# 222.net
KiCad netlist of a schematic drawn in Altium Designer
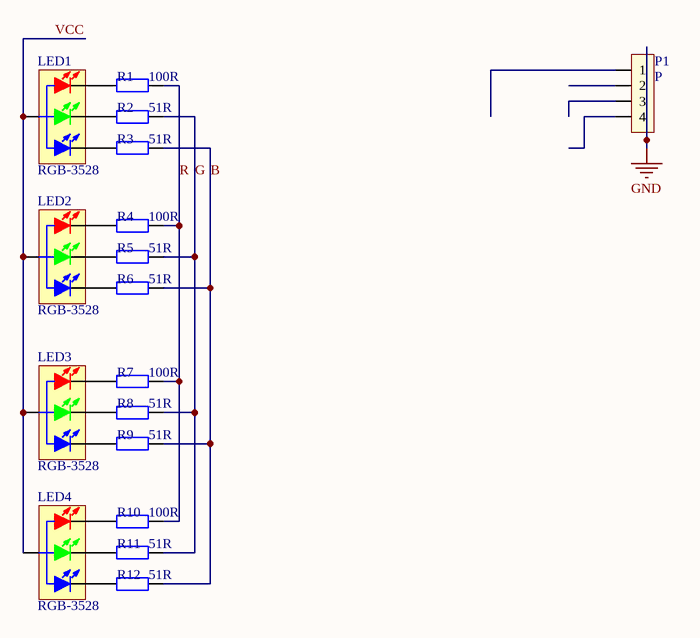
[diagram p0: 222.SchDoc]

(export (version "E")
  (design (tool "Eeschema 10.0.6"))
  (components
    (comp (ref "LED1")
      (value "RGB-3528")
      (footprint "LED 3528-4Pin")
      (description "三基色LED")
      (libsource (lib "9.1   - LED") (part "LED-RGB-3528"))
    )
    (comp (ref "LED2")
      (value "RGB-3528")
      (footprint "LED 3528-4Pin")
      (description "三基色LED")
      (libsource (lib "9.1   - LED") (part "LED-RGB-3528"))
    )
    (comp (ref "LED3")
      (value "RGB-3528")
      (footprint "LED 3528-4Pin")
      (description "三基色LED")
      (libsource (lib "9.1   - LED") (part "LED-RGB-3528"))
    )
    (comp (ref "LED4")
      (value "RGB-3528")
      (footprint "LED 3528-4Pin")
      (description "三基色LED")
      (libsource (lib "9.1   - LED") (part "LED-RGB-3528"))
    )
    (comp (ref "P1") (value "P") (footprint "SH1.0_4pin") (libsource (lib "0") (part "SH1.0-4")))
    (comp (ref "R1")
      (value "100R")
      (footprint "0603-1")
      (description "贴片电阻")
      (fields (field (name "Comment") "Res1") (field (name "PUBLISHER") "Altium Limited"))
      (libsource (lib "fszhang") (part "Res1"))
    )
    (comp (ref "R2")
      (value "51R")
      (footprint "0603-1")
      (description "贴片电阻")
      (fields (field (name "Comment") "Res1") (field (name "PUBLISHER") "Altium Limited"))
      (libsource (lib "fszhang") (part "Res1"))
    )
    (comp (ref "R3")
      (value "51R")
      (footprint "0603-1")
      (description "贴片电阻")
      (fields (field (name "Comment") "Res1") (field (name "PUBLISHER") "Altium Limited"))
      (libsource (lib "fszhang") (part "Res1"))
    )
    (comp (ref "R4")
      (value "100R")
      (footprint "0603-1")
      (description "贴片电阻")
      (fields (field (name "Comment") "Res1") (field (name "PUBLISHER") "Altium Limited"))
      (libsource (lib "fszhang") (part "Res1"))
    )
    (comp (ref "R5")
      (value "51R")
      (footprint "0603-1")
      (description "贴片电阻")
      (fields (field (name "Comment") "Res1") (field (name "PUBLISHER") "Altium Limited"))
      (libsource (lib "fszhang") (part "Res1"))
    )
    (comp (ref "R6")
      (value "51R")
      (footprint "0603-1")
      (description "贴片电阻")
      (fields (field (name "Comment") "Res1") (field (name "PUBLISHER") "Altium Limited"))
      (libsource (lib "fszhang") (part "Res1"))
    )
    (comp (ref "R7")
      (value "100R")
      (footprint "0603-1")
      (description "贴片电阻")
      (fields (field (name "Comment") "Res1") (field (name "PUBLISHER") "Altium Limited"))
      (libsource (lib "fszhang") (part "Res1"))
    )
    (comp (ref "R8")
      (value "51R")
      (footprint "0603-1")
      (description "贴片电阻")
      (fields (field (name "Comment") "Res1") (field (name "PUBLISHER") "Altium Limited"))
      (libsource (lib "fszhang") (part "Res1"))
    )
    (comp (ref "R9")
      (value "51R")
      (footprint "0603-1")
      (description "贴片电阻")
      (fields (field (name "Comment") "Res1") (field (name "PUBLISHER") "Altium Limited"))
      (libsource (lib "fszhang") (part "Res1"))
    )
    (comp (ref "R10")
      (value "100R")
      (footprint "0603-1")
      (description "贴片电阻")
      (fields (field (name "Comment") "Res1") (field (name "PUBLISHER") "Altium Limited"))
      (libsource (lib "fszhang") (part "Res1"))
    )
    (comp (ref "R11")
      (value "51R")
      (footprint "0603-1")
      (description "贴片电阻")
      (fields (field (name "Comment") "Res1") (field (name "PUBLISHER") "Altium Limited"))
      (libsource (lib "fszhang") (part "Res1"))
    )
    (comp (ref "R12")
      (value "51R")
      (footprint "0603-1")
      (description "贴片电阻")
      (fields (field (name "Comment") "Res1") (field (name "PUBLISHER") "Altium Limited"))
      (libsource (lib "fszhang") (part "Res1"))
    )
  )
  (nets
    (net (code "1") (name "/B") (class "Default")
      (node (ref "R12") (pin "2") (pinfunction "2_2") (pintype "passive"))
      (node (ref "R3") (pin "2") (pinfunction "2_2") (pintype "passive"))
      (node (ref "R6") (pin "2") (pinfunction "2_2") (pintype "passive"))
      (node (ref "R9") (pin "2") (pinfunction "2_2") (pintype "passive"))
    )
    (net (code "2") (name "/G") (class "Default")
      (node (ref "R11") (pin "2") (pinfunction "2_2") (pintype "passive"))
      (node (ref "R2") (pin "2") (pinfunction "2_2") (pintype "passive"))
      (node (ref "R5") (pin "2") (pinfunction "2_2") (pintype "passive"))
      (node (ref "R8") (pin "2") (pinfunction "2_2") (pintype "passive"))
    )
    (net (code "3") (name "/R") (class "Default")
      (node (ref "R1") (pin "2") (pinfunction "2_2") (pintype "passive"))
      (node (ref "R10") (pin "2") (pinfunction "2_2") (pintype "passive"))
      (node (ref "R4") (pin "2") (pinfunction "2_2") (pintype "passive"))
      (node (ref "R7") (pin "2") (pinfunction "2_2") (pintype "passive"))
    )
    (net (code "4") (name "/VCC") (class "Default")
      (node (ref "LED1") (pin "4") (pinfunction "A_4") (pintype "passive"))
      (node (ref "LED2") (pin "4") (pinfunction "A_4") (pintype "passive"))
      (node (ref "LED3") (pin "4") (pinfunction "A_4") (pintype "passive"))
      (node (ref "LED4") (pin "4") (pinfunction "A_4") (pintype "passive"))
    )
    (net (code "5") (name "GND") (class "Default")
      (node (ref "P1") (pin "0") (pinfunction "0_0") (pintype "passive"))
    )
    (net (code "6") (name "Net-(LED1-BULE_K)") (class "Default")
      (node (ref "LED1") (pin "3") (pinfunction "BULE_K_3") (pintype "passive"))
      (node (ref "R3") (pin "1") (pinfunction "1_1") (pintype "passive"))
    )
    (net (code "7") (name "Net-(LED1-GREEN_K)") (class "Default")
      (node (ref "LED1") (pin "2") (pinfunction "GREEN_K_2") (pintype "passive"))
      (node (ref "R2") (pin "1") (pinfunction "1_1") (pintype "passive"))
    )
    (net (code "8") (name "Net-(LED1-RED_K)") (class "Default")
      (node (ref "LED1") (pin "1") (pinfunction "RED_K_1") (pintype "passive"))
      (node (ref "R1") (pin "1") (pinfunction "1_1") (pintype "passive"))
    )
    (net (code "9") (name "Net-(LED2-BULE_K)") (class "Default")
      (node (ref "LED2") (pin "3") (pinfunction "BULE_K_3") (pintype "passive"))
      (node (ref "R6") (pin "1") (pinfunction "1_1") (pintype "passive"))
    )
    (net (code "10") (name "Net-(LED2-GREEN_K)") (class "Default")
      (node (ref "LED2") (pin "2") (pinfunction "GREEN_K_2") (pintype "passive"))
      (node (ref "R5") (pin "1") (pinfunction "1_1") (pintype "passive"))
    )
    (net (code "11") (name "Net-(LED2-RED_K)") (class "Default")
      (node (ref "LED2") (pin "1") (pinfunction "RED_K_1") (pintype "passive"))
      (node (ref "R4") (pin "1") (pinfunction "1_1") (pintype "passive"))
    )
    (net (code "12") (name "Net-(LED3-BULE_K)") (class "Default")
      (node (ref "LED3") (pin "3") (pinfunction "BULE_K_3") (pintype "passive"))
      (node (ref "R9") (pin "1") (pinfunction "1_1") (pintype "passive"))
    )
    (net (code "13") (name "Net-(LED3-GREEN_K)") (class "Default")
      (node (ref "LED3") (pin "2") (pinfunction "GREEN_K_2") (pintype "passive"))
      (node (ref "R8") (pin "1") (pinfunction "1_1") (pintype "passive"))
    )
    (net (code "14") (name "Net-(LED3-RED_K)") (class "Default")
      (node (ref "LED3") (pin "1") (pinfunction "RED_K_1") (pintype "passive"))
      (node (ref "R7") (pin "1") (pinfunction "1_1") (pintype "passive"))
    )
    (net (code "15") (name "Net-(LED4-BULE_K)") (class "Default")
      (node (ref "LED4") (pin "3") (pinfunction "BULE_K_3") (pintype "passive"))
      (node (ref "R12") (pin "1") (pinfunction "1_1") (pintype "passive"))
    )
    (net (code "16") (name "Net-(LED4-GREEN_K)") (class "Default")
      (node (ref "LED4") (pin "2") (pinfunction "GREEN_K_2") (pintype "passive"))
      (node (ref "R11") (pin "1") (pinfunction "1_1") (pintype "passive"))
    )
    (net (code "17") (name "Net-(LED4-RED_K)") (class "Default")
      (node (ref "LED4") (pin "1") (pinfunction "RED_K_1") (pintype "passive"))
      (node (ref "R10") (pin "1") (pinfunction "1_1") (pintype "passive"))
    )
    (net (code "18") (name "unconnected-(P1-Pad1)") (class "Default")
      (node (ref "P1") (pin "1") (pinfunction "1_1") (pintype "passive"))
    )
    (net (code "19") (name "unconnected-(P1-Pad2)") (class "Default")
      (node (ref "P1") (pin "2") (pinfunction "2_2") (pintype "passive"))
    )
    (net (code "20") (name "unconnected-(P1-Pad3)") (class "Default")
      (node (ref "P1") (pin "3") (pinfunction "3_3") (pintype "passive"))
    )
    (net (code "21") (name "unconnected-(P1-Pad4)") (class "Default")
      (node (ref "P1") (pin "4") (pinfunction "4_4") (pintype "passive"))
    )
  )
)
